# flashlight.net
KiCad netlist of a schematic drawn in EAGLE
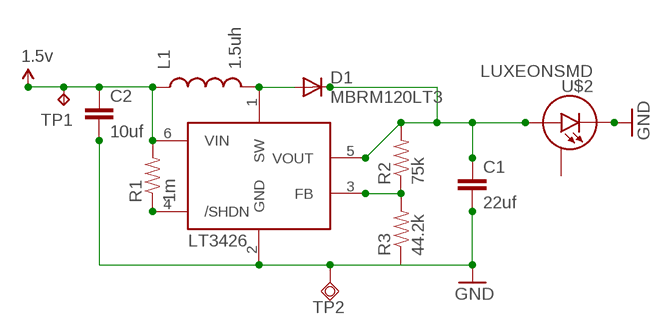
[diagram p0: schematic, sheet 1]

(export (version "E")
  (design (tool "Eeschema 10.0.6"))
  (components
    (comp (ref "C1")
      (value "22uf")
      (footprint "eagle-import:0805")
      (libsource (lib "eagle-import") (part "CAP0805"))
    )
    (comp (ref "C2")
      (value "10uf")
      (footprint "eagle-import:0805")
      (libsource (lib "eagle-import") (part "CAP0805"))
    )
    (comp (ref "D1")
      (value "MBRM120LT3")
      (footprint "eagle-import:SOD80C")
      (libsource (lib "eagle-import") (part "PMLL4150"))
    )
    (comp (ref "L1")
      (value "1.5uh")
      (footprint "eagle-import:1007")
      (libsource (lib "eagle-import") (part "INDUCTOR1007"))
    )
    (comp (ref "R1")
      (value "1m")
      (footprint "eagle-import:0805")
      (libsource (lib "eagle-import") (part "RESISTOR0805-RES"))
    )
    (comp (ref "R2")
      (value "75k")
      (footprint "eagle-import:0805")
      (libsource (lib "eagle-import") (part "RESISTOR0805-RES"))
    )
    (comp (ref "R3")
      (value "44.2k")
      (footprint "eagle-import:0805")
      (libsource (lib "eagle-import") (part "RESISTOR0805-RES"))
    )
    (comp (ref "TP1")
      (value "TPTP20R")
      (footprint "eagle-import:TP20R")
      (libsource (lib "eagle-import") (part "TPTP20R"))
    )
    (comp (ref "TP2")
      (value "TPSQPAD1-13")
      (footprint "eagle-import:P1-13")
      (libsource (lib "eagle-import") (part "TPSQPAD1-13"))
    )
    (comp (ref "U$1")
      (value "LT3426")
      (footprint "eagle-import:SOT23-6")
      (libsource (lib "eagle-import") (part "LT3426"))
    )
    (comp (ref "U$2")
      (value "LUXEONSMD")
      (footprint "eagle-import:LUXEON")
      (libsource (lib "eagle-import") (part "LUXEONSMD"))
    )
  )
  (nets
    (net (code "1") (name "1.5v") (class "Default")
      (node (ref "C2") (pin "1") (pinfunction "1_1") (pintype "passive"))
      (node (ref "L1") (pin "1") (pinfunction "1_1") (pintype "passive"))
      (node (ref "R1") (pin "2") (pinfunction "2_2") (pintype "passive"))
      (node (ref "TP1") (pin "TP") (pinfunction "TP_TP") (pintype "input"))
      (node (ref "U$1") (pin "6") (pinfunction "VIN_6") (pintype "input"))
    )
    (net (code "2") (name "GND") (class "Default")
      (node (ref "C1") (pin "2") (pinfunction "2_2") (pintype "passive"))
      (node (ref "C2") (pin "2") (pinfunction "2_2") (pintype "passive"))
      (node (ref "R3") (pin "1") (pinfunction "1_1") (pintype "passive"))
      (node (ref "TP2") (pin "TP") (pinfunction "TP_TP") (pintype "input"))
      (node (ref "U$1") (pin "2") (pinfunction "GND_2") (pintype "power_in"))
      (node (ref "U$2") (pin "C") (pinfunction "C_C") (pintype "passive"))
    )
    (net (code "3") (name "Net-(U$1-FB)") (class "Default")
      (node (ref "R2") (pin "1") (pinfunction "1_1") (pintype "passive"))
      (node (ref "R3") (pin "2") (pinfunction "2_2") (pintype "passive"))
      (node (ref "U$1") (pin "3") (pinfunction "FB_3") (pintype "input"))
    )
    (net (code "4") (name "Net-(U$1-SW)") (class "Default")
      (node (ref "D1") (pin "A") (pinfunction "A_A") (pintype "passive"))
      (node (ref "L1") (pin "2") (pinfunction "2_2") (pintype "passive"))
      (node (ref "U$1") (pin "1") (pinfunction "SW_1") (pintype "output"))
    )
    (net (code "5") (name "Net-(U$1-VOUT)") (class "Default")
      (node (ref "C1") (pin "1") (pinfunction "1_1") (pintype "passive"))
      (node (ref "D1") (pin "C") (pinfunction "C_C") (pintype "passive"))
      (node (ref "R2") (pin "2") (pinfunction "2_2") (pintype "passive"))
      (node (ref "U$1") (pin "5") (pinfunction "VOUT_5") (pintype "output"))
      (node (ref "U$2") (pin "A") (pinfunction "A_A") (pintype "passive"))
    )
    (net (code "6") (name "Net-(U$1-{slash}SHDN)") (class "Default")
      (node (ref "R1") (pin "1") (pinfunction "1_1") (pintype "passive"))
      (node (ref "U$1") (pin "4") (pinfunction "/SHDN_4") (pintype "input"))
    )
    (net (code "7") (name "unconnected-(U$2-PadS)") (class "Default")
      (node (ref "U$2") (pin "S") (pinfunction "S_S") (pintype "bidirectional"))
    )
  )
)
